# MA-Power.net
KiCad netlist of a schematic drawn in Altium Designer
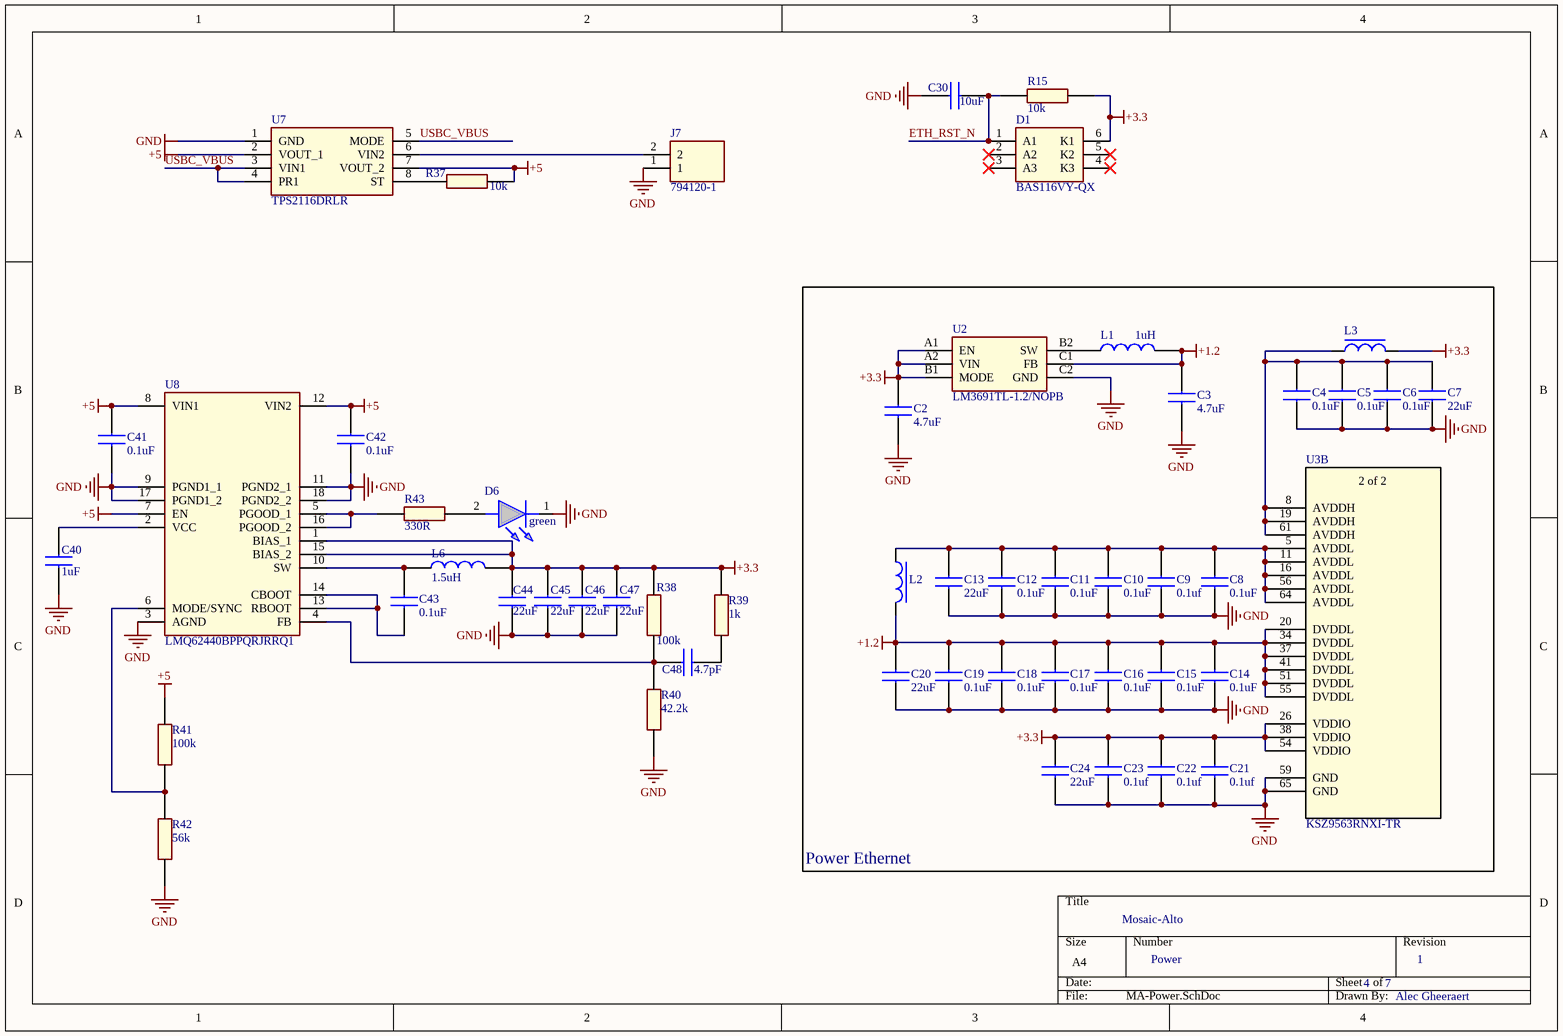
[diagram p0: MA-Power.SchDoc]

(export (version "E")
  (design (tool "Eeschema 10.0.6"))
  (components
    (comp (ref "C2")
      (value "4.7uF")
      (footprint "CAPC1608X100N")
      (description "0603 4.7µF")
      (fields (field (name "MANUFACTURER") "Walsin") (field (name "TOLERANCE") "20%"))
      (libsource (lib "Ghrt") (part "0603X475M6R3CT"))
    )
    (comp (ref "C3")
      (value "4.7uF")
      (footprint "CAPC1608X100N")
      (description "0603 4.7µF")
      (fields (field (name "MANUFACTURER") "Walsin") (field (name "TOLERANCE") "20%"))
      (libsource (lib "Ghrt") (part "0603X475M6R3CT"))
    )
    (comp (ref "C4")
      (value "0.1uF")
      (footprint "CAPC1005X55N")
      (description "0402I 0.1µF")
      (fields (field (name "MANUFACTURER") "Walsin") (field (name "TOLERANCE") "10%"))
      (libsource (lib "Ghrt") (part "MG15B104K100CT"))
    )
    (comp (ref "C5")
      (value "0.1uF")
      (footprint "CAPC1005X55N")
      (description "0402I 0.1µF")
      (fields (field (name "MANUFACTURER") "Walsin") (field (name "TOLERANCE") "10%"))
      (libsource (lib "Ghrt") (part "MG15B104K100CT"))
    )
    (comp (ref "C6")
      (value "0.1uF")
      (footprint "CAPC1005X55N")
      (description "0402I 0.1µF")
      (fields (field (name "MANUFACTURER") "Walsin") (field (name "TOLERANCE") "10%"))
      (libsource (lib "Ghrt") (part "MG15B104K100CT"))
    )
    (comp (ref "C7")
      (value "22uF")
      (footprint "CAPC2012X145N")
      (description "0805 22µF")
      (fields (field (name "MANUFACTURER") "Walsin") (field (name "TOLERANCE") "10%"))
      (libsource (lib "Ghrt") (part "0805X226K6R3CT"))
    )
    (comp (ref "C8")
      (value "0.1uF")
      (footprint "CAPC1005X55N")
      (description "0402I 0.1µF")
      (fields (field (name "MANUFACTURER") "Walsin") (field (name "TOLERANCE") "10%"))
      (libsource (lib "Ghrt") (part "MG15B104K100CT"))
    )
    (comp (ref "C9")
      (value "0.1uf")
      (footprint "CAPC1005X55N")
      (description "0402I 0.1µF")
      (fields (field (name "MANUFACTURER") "Walsin") (field (name "TOLERANCE") "10%"))
      (libsource (lib "Ghrt") (part "MG15B104K100CT"))
    )
    (comp (ref "C10")
      (value "0.1uF")
      (footprint "CAPC1005X55N")
      (description "0402I 0.1µF")
      (fields (field (name "MANUFACTURER") "Walsin") (field (name "TOLERANCE") "10%"))
      (libsource (lib "Ghrt") (part "MG15B104K100CT"))
    )
    (comp (ref "C11")
      (value "0.1uF")
      (footprint "CAPC1005X55N")
      (description "0402I 0.1µF")
      (fields (field (name "MANUFACTURER") "Walsin") (field (name "TOLERANCE") "10%"))
      (libsource (lib "Ghrt") (part "MG15B104K100CT"))
    )
    (comp (ref "C12")
      (value "0.1uF")
      (footprint "CAPC1005X55N")
      (description "0402I 0.1µF")
      (fields (field (name "MANUFACTURER") "Walsin") (field (name "TOLERANCE") "10%"))
      (libsource (lib "Ghrt") (part "MG15B104K100CT"))
    )
    (comp (ref "C13")
      (value "22uF")
      (footprint "CAPC2012X145N")
      (description "0805 22µF")
      (fields (field (name "MANUFACTURER") "Walsin") (field (name "TOLERANCE") "10%"))
      (libsource (lib "Ghrt") (part "0805X226K6R3CT"))
    )
    (comp (ref "C14")
      (value "0.1uF")
      (footprint "CAPC1005X55N")
      (description "0402I 0.1µF")
      (fields (field (name "MANUFACTURER") "Walsin") (field (name "TOLERANCE") "10%"))
      (libsource (lib "Ghrt") (part "MG15B104K100CT"))
    )
    (comp (ref "C15")
      (value "0.1uF")
      (footprint "CAPC1005X55N")
      (description "0402I 0.1µF")
      (fields (field (name "MANUFACTURER") "Walsin") (field (name "TOLERANCE") "10%"))
      (libsource (lib "Ghrt") (part "MG15B104K100CT"))
    )
    (comp (ref "C16")
      (value "0.1uF")
      (footprint "CAPC1005X55N")
      (description "0402I 0.1µF")
      (fields (field (name "MANUFACTURER") "Walsin") (field (name "TOLERANCE") "10%"))
      (libsource (lib "Ghrt") (part "MG15B104K100CT"))
    )
    (comp (ref "C17")
      (value "0.1uF")
      (footprint "CAPC1005X55N")
      (description "0402I 0.1µF")
      (fields (field (name "MANUFACTURER") "Walsin") (field (name "TOLERANCE") "10%"))
      (libsource (lib "Ghrt") (part "MG15B104K100CT"))
    )
    (comp (ref "C18")
      (value "0.1uF")
      (footprint "CAPC1005X55N")
      (description "0402I 0.1µF")
      (fields (field (name "MANUFACTURER") "Walsin") (field (name "TOLERANCE") "10%"))
      (libsource (lib "Ghrt") (part "MG15B104K100CT"))
    )
    (comp (ref "C19")
      (value "0.1uF")
      (footprint "CAPC1005X55N")
      (description "0402I 0.1µF")
      (fields (field (name "MANUFACTURER") "Walsin") (field (name "TOLERANCE") "10%"))
      (libsource (lib "Ghrt") (part "MG15B104K100CT"))
    )
    (comp (ref "C20")
      (value "22uF")
      (footprint "CAPC2012X145N")
      (description "0805 22µF")
      (fields (field (name "MANUFACTURER") "Walsin") (field (name "TOLERANCE") "10%"))
      (libsource (lib "Ghrt") (part "0805X226K6R3CT"))
    )
    (comp (ref "C21")
      (value "0.1uf")
      (footprint "CAPC1005X55N")
      (description "0402I 0.1µF")
      (fields (field (name "MANUFACTURER") "Walsin") (field (name "TOLERANCE") "10%"))
      (libsource (lib "Ghrt") (part "MG15B104K100CT"))
    )
    (comp (ref "C22")
      (value "0.1uf")
      (footprint "CAPC1005X55N")
      (description "0402I 0.1µF")
      (fields (field (name "MANUFACTURER") "Walsin") (field (name "TOLERANCE") "10%"))
      (libsource (lib "Ghrt") (part "MG15B104K100CT"))
    )
    (comp (ref "C23")
      (value "0.1uf")
      (footprint "CAPC1005X55N")
      (description "0402I 0.1µF")
      (fields (field (name "MANUFACTURER") "Walsin") (field (name "TOLERANCE") "10%"))
      (libsource (lib "Ghrt") (part "MG15B104K100CT"))
    )
    (comp (ref "C24")
      (value "22uF")
      (footprint "CAPC2012X145N")
      (description "0805 22µF")
      (fields (field (name "MANUFACTURER") "Walsin") (field (name "TOLERANCE") "10%"))
      (libsource (lib "Ghrt") (part "0805X226K6R3CT"))
    )
    (comp (ref "C30")
      (value "10uF")
      (footprint "CAPC1608X100N")
      (description "0603 10µF")
      (fields (field (name "MANUFACTURER") "Walsin") (field (name "TOLERANCE") "10%"))
      (libsource (lib "Ghrt") (part "0603X106K6R3CT"))
    )
    (comp (ref "C40")
      (value "1uF")
      (footprint "CAPC1608X100N")
      (description "0603 1µF")
      (fields (field (name "MANUFACTURER") "Walsin") (field (name "TOLERANCE") "10%"))
      (libsource (lib "Ghrt") (part "0603X105K6R3CT"))
    )
    (comp (ref "C41")
      (value "0.1uF")
      (footprint "CAPC2012X145N")
      (description "0805I 0.1µF")
      (fields (field (name "MANUFACTURER") "Walsin") (field (name "TOLERANCE") "10%"))
      (libsource (lib "Ghrt") (part "MG21B104K101CT"))
    )
    (comp (ref "C42")
      (value "0.1uF")
      (footprint "CAPC2012X145N")
      (description "0805I 0.1µF")
      (fields (field (name "MANUFACTURER") "Walsin") (field (name "TOLERANCE") "10%"))
      (libsource (lib "Ghrt") (part "MG21B104K101CT"))
    )
    (comp (ref "C43")
      (value "0.1uF")
      (footprint "CAPC1005X55N")
      (description "0402I 0.1µF")
      (fields (field (name "MANUFACTURER") "Walsin") (field (name "TOLERANCE") "10%"))
      (libsource (lib "Ghrt") (part "MG15B104K100CT"))
    )
    (comp (ref "C44")
      (value "22uF")
      (footprint "CAPC2012X145N")
      (description "0805 22µF")
      (fields (field (name "MANUFACTURER") "Walsin") (field (name "TOLERANCE") "10%"))
      (libsource (lib "Ghrt") (part "0805X226K6R3CT"))
    )
    (comp (ref "C45")
      (value "22uF")
      (footprint "CAPC2012X145N")
      (description "0805 22µF")
      (fields (field (name "MANUFACTURER") "Walsin") (field (name "TOLERANCE") "10%"))
      (libsource (lib "Ghrt") (part "0805X226K6R3CT"))
    )
    (comp (ref "C46")
      (value "22uF")
      (footprint "CAPC2012X145N")
      (description "0805 22µF")
      (fields (field (name "MANUFACTURER") "Walsin") (field (name "TOLERANCE") "10%"))
      (libsource (lib "Ghrt") (part "0805X226K6R3CT"))
    )
    (comp (ref "C47")
      (value "22uF")
      (footprint "CAPC2012X145N")
      (description "0805 22µF")
      (fields (field (name "MANUFACTURER") "Walsin") (field (name "TOLERANCE") "10%"))
      (libsource (lib "Ghrt") (part "0805X226K6R3CT"))
    )
    (comp (ref "C48")
      (value "4.7pF")
      (footprint "CAPC1608X87N")
      (description "0603 4.7pF")
      (fields (field (name "TOLERANCE") "5%") (field (name "MANUFACTURER") "Walsin"))
      (libsource (lib "Ghrt") (part "0603N4R7B500CT"))
    )
    (comp (ref "D1")
      (value "BAS116VY-QX")
      (footprint "BAS116VYQX")
      (description "Triple Diode Array")
      (fields (field (name "MANUFACTURER") "Nexperia"))
      (libsource (lib "Ghrt") (part "BAS116VY-QX"))
    )
    (comp (ref "D6")
      (value "green")
      (footprint "APT1608ZGCAMT")
      (description "0603 Green LED")
      (libsource (lib "Ghrt") (part "APT1608ZGC-AMT"))
    )
    (comp (ref "J7")
      (value "794120-1")
      (footprint "7941201")
      (description "Right Angle PCB Header")
      (libsource (lib "Ghrt") (part "794120-1"))
    )
    (comp (ref "L1")
      (value "1uH")
      (footprint "INDC2016X100N")
      (description "1µH Inductor")
      (fields (field (name "TOLERANCE") "20%") (field (name "MANUFACTURER") "TDK"))
      (libsource (lib "Ghrt") (part "MLP2016H1R0MT0S1"))
    )
    (comp (ref "L2")
      (value "MPZ1608S121ATDH5")
      (footprint "BEADC1608X75N")
      (description "0603I 120ohms Ferrite Bead")
      (fields (field (name "TOLERANCE") "25%") (field (name "MANUFACTURER") "TDK"))
      (libsource (lib "Ghrt") (part "MPZ1608S121ATDH5"))
    )
    (comp (ref "L3")
      (value "MPZ1608S121ATDH5")
      (footprint "BEADC1608X75N")
      (description "0603I 120ohms Ferrite Bead")
      (fields (field (name "TOLERANCE") "25%") (field (name "MANUFACTURER") "TDK"))
      (libsource (lib "Ghrt") (part "MPZ1608S121ATDH5"))
    )
    (comp (ref "L6")
      (value "1.5uH")
      (footprint "INDC1005X55N")
      (description "1.5uH Inductor")
      (libsource (lib "Ghrt") (part "MLF1005G1R5JTD25"))
    )
    (comp (ref "R15")
      (value "10k")
      (footprint "RESC1005X40N")
      (description "0402I 10k")
      (fields (field (name "MANUFACTURER") "Walsin") (field (name "TOLERANCE") "1%"))
      (libsource (lib "") (part "WR04X1002FTL_1"))
    )
    (comp (ref "R37")
      (value "10k")
      (footprint "RESC1005X40N")
      (description "0402I 10k")
      (fields (field (name "MANUFACTURER") "Walsin") (field (name "TOLERANCE") "1%"))
      (libsource (lib "Ghrt") (part "WR04X1002FTL"))
    )
    (comp (ref "R38")
      (value "100k")
      (footprint "RESC1005X40N")
      (description "0402I 100k")
      (fields (field (name "MANUFACTURER") "Walsin") (field (name "TOLERANCE") "1%"))
      (libsource (lib "") (part "WR04X1003FTL_1"))
    )
    (comp (ref "R39")
      (value "1k")
      (footprint "RESC1005X40N")
      (description "0402I 1k")
      (fields (field (name "MANUFACTURER") "Walsin") (field (name "TOLERANCE") "1%"))
      (libsource (lib "Ghrt") (part "WR04X1001FTL"))
    )
    (comp (ref "R40")
      (value "42.2k")
      (footprint "RESC1005X40N")
      (description "0402I 42.2k")
      (fields (field (name "TOLERANCE") "1%") (field (name "MANUFACTURER") "Walsin"))
      (libsource (lib "Ghrt") (part "WR04X4222FTL"))
    )
    (comp (ref "R41")
      (value "100k")
      (footprint "RESC1005X40N")
      (description "0402I 100k")
      (fields (field (name "MANUFACTURER") "Walsin") (field (name "TOLERANCE") "1%"))
      (libsource (lib "Ghrt") (part "WR04X1003FTL"))
    )
    (comp (ref "R42")
      (value "56k")
      (footprint "RESC1005X40N")
      (description "0402I 56k")
      (fields (field (name "TOLERANCE") "1%") (field (name "MANUFACTURER") "Walsin"))
      (libsource (lib "Ghrt") (part "WR04X5602FTL"))
    )
    (comp (ref "R43")
      (value "330R")
      (footprint "RESC1005X40N")
      (description "0402I 330")
      (fields (field (name "TOLERANCE") "1%") (field (name "MANUFACTURER") "Walsin"))
      (libsource (lib "Ghrt") (part "WR04X3300FTL"))
    )
    (comp (ref "U2")
      (value "LM3691TL-1.2/NOPB")
      (footprint "BGA6C50P2X3_126X156X68")
      (description "1.2V 1A Buck Converter")
      (fields (field (name "MANUFACTURER") "Texas Instruments"))
      (libsource (lib "Ghrt") (part "LM3691TL-1.2_NOPB"))
    )
    (comp (ref "U3")
      (value "KSZ9563RNXI-TR")
      (footprint "VQFN64_NX_MCH")
      (description "3-Port Gigabit Ethernet Switch")
      (fields (field (name "MANUFACTURER") "Texas Instruments"))
      (libsource (lib "Ghrt") (part "KSZ9563RNXI-TR"))
    )
    (comp (ref "U7")
      (value "TPS2116DRLR")
      (footprint "SOTFL50P160X60-8N")
      (description "2.5A Power Multiplexer")
      (fields (field (name "MANUFACTURER") "Texas Instruments"))
      (libsource (lib "Ghrt") (part "TPS2116DRLR"))
    )
    (comp (ref "U8")
      (value "LMQ62440BPPQRJRRQ1")
      (footprint "LMQ62440BPPQRJRRQ1")
      (description "3.3V 4A Switching Voltage Regulator")
      (fields (field (name "MANUFACTURER") "Texas Instruments"))
      (libsource (lib "Ghrt") (part "LMQ62440BPPQRJRRQ1"))
    )
  )
  (nets
    (net (code "1") (name "+1.2") (class "Default")
      (node (ref "C14") (pin "1") (pinfunction "1_1") (pintype "passive"))
      (node (ref "C15") (pin "1") (pinfunction "1_1") (pintype "passive"))
      (node (ref "C16") (pin "1") (pinfunction "1_1") (pintype "passive"))
      (node (ref "C17") (pin "1") (pinfunction "1_1") (pintype "passive"))
      (node (ref "C18") (pin "1") (pinfunction "1_1") (pintype "passive"))
      (node (ref "C19") (pin "1") (pinfunction "1_1") (pintype "passive"))
      (node (ref "C20") (pin "1") (pinfunction "1_1") (pintype "passive"))
      (node (ref "C3") (pin "1") (pinfunction "1_1") (pintype "passive"))
      (node (ref "L1") (pin "2") (pinfunction "2_2") (pintype "passive"))
      (node (ref "L2") (pin "2") (pinfunction "2_2") (pintype "passive"))
      (node (ref "U2") (pin "C1") (pinfunction "FB_C1") (pintype "passive"))
      (node (ref "U3") (pin "20") (pinfunction "DVDDL_20") (pintype "power_in"))
      (node (ref "U3") (pin "34") (pinfunction "DVDDL_34") (pintype "power_in"))
      (node (ref "U3") (pin "37") (pinfunction "DVDDL_37") (pintype "power_in"))
      (node (ref "U3") (pin "41") (pinfunction "DVDDL_41") (pintype "power_in"))
      (node (ref "U3") (pin "51") (pinfunction "DVDDL_51") (pintype "power_in"))
      (node (ref "U3") (pin "55") (pinfunction "DVDDL_55") (pintype "power_in"))
    )
    (net (code "2") (name "+3.3") (class "Default")
      (node (ref "C2") (pin "1") (pinfunction "1_1") (pintype "passive"))
      (node (ref "C21") (pin "1") (pinfunction "1_1") (pintype "passive"))
      (node (ref "C22") (pin "1") (pinfunction "1_1") (pintype "passive"))
      (node (ref "C23") (pin "1") (pinfunction "1_1") (pintype "passive"))
      (node (ref "C24") (pin "1") (pinfunction "1_1") (pintype "passive"))
      (node (ref "C44") (pin "1") (pinfunction "1_1") (pintype "passive"))
      (node (ref "C45") (pin "1") (pinfunction "1_1") (pintype "passive"))
      (node (ref "C46") (pin "1") (pinfunction "1_1") (pintype "passive"))
      (node (ref "C47") (pin "1") (pinfunction "1_1") (pintype "passive"))
      (node (ref "D1") (pin "6") (pinfunction "K1_6") (pintype "passive"))
      (node (ref "L3") (pin "2") (pinfunction "2_2") (pintype "passive"))
      (node (ref "L6") (pin "2") (pinfunction "2_2") (pintype "passive"))
      (node (ref "R15") (pin "1") (pinfunction "1_1") (pintype "passive"))
      (node (ref "R38") (pin "1") (pinfunction "1_1") (pintype "passive"))
      (node (ref "R39") (pin "2") (pinfunction "2_2") (pintype "passive"))
      (node (ref "U2") (pin "A1") (pinfunction "EN_A1") (pintype "passive"))
      (node (ref "U2") (pin "A2") (pinfunction "VIN_A2") (pintype "passive"))
      (node (ref "U2") (pin "B1") (pinfunction "MODE_B1") (pintype "passive"))
      (node (ref "U3") (pin "26") (pinfunction "VDDIO_26") (pintype "power_in"))
      (node (ref "U3") (pin "38") (pinfunction "VDDIO_38") (pintype "power_in"))
      (node (ref "U3") (pin "54") (pinfunction "VDDIO_54") (pintype "power_in"))
      (node (ref "U8") (pin "1") (pinfunction "BIAS_1_1") (pintype "passive"))
      (node (ref "U8") (pin "15") (pinfunction "BIAS_2_15") (pintype "passive"))
    )
    (net (code "3") (name "+5") (class "Default")
      (node (ref "C41") (pin "1") (pinfunction "1_1") (pintype "passive"))
      (node (ref "C42") (pin "1") (pinfunction "1_1") (pintype "passive"))
      (node (ref "R37") (pin "2") (pinfunction "2_2") (pintype "passive"))
      (node (ref "R41") (pin "2") (pinfunction "2_2") (pintype "passive"))
      (node (ref "U7") (pin "2") (pinfunction "VOUT_1_2") (pintype "passive"))
      (node (ref "U7") (pin "7") (pinfunction "VOUT_2_7") (pintype "passive"))
      (node (ref "U8") (pin "12") (pinfunction "VIN2_12") (pintype "passive"))
      (node (ref "U8") (pin "7") (pinfunction "EN_7") (pintype "passive"))
      (node (ref "U8") (pin "8") (pinfunction "VIN1_8") (pintype "passive"))
    )
    (net (code "4") (name "/ETH_RST_N") (class "Default")
      (node (ref "C30") (pin "1") (pinfunction "1_1") (pintype "passive"))
      (node (ref "D1") (pin "1") (pinfunction "A1_1") (pintype "passive"))
      (node (ref "R15") (pin "2") (pinfunction "2_2") (pintype "passive"))
    )
    (net (code "5") (name "/USBC_VBUS") (class "Default")
      (node (ref "U7") (pin "3") (pinfunction "VIN1_3") (pintype "passive"))
      (node (ref "U7") (pin "4") (pinfunction "PR1_4") (pintype "passive"))
      (node (ref "U7") (pin "5") (pinfunction "MODE_5") (pintype "passive"))
    )
    (net (code "6") (name "GND") (class "Default")
      (node (ref "C10") (pin "2") (pinfunction "2_2") (pintype "passive"))
      (node (ref "C11") (pin "2") (pinfunction "2_2") (pintype "passive"))
      (node (ref "C12") (pin "2") (pinfunction "2_2") (pintype "passive"))
      (node (ref "C13") (pin "2") (pinfunction "2_2") (pintype "passive"))
      (node (ref "C14") (pin "2") (pinfunction "2_2") (pintype "passive"))
      (node (ref "C15") (pin "2") (pinfunction "2_2") (pintype "passive"))
      (node (ref "C16") (pin "2") (pinfunction "2_2") (pintype "passive"))
      (node (ref "C17") (pin "2") (pinfunction "2_2") (pintype "passive"))
      (node (ref "C18") (pin "2") (pinfunction "2_2") (pintype "passive"))
      (node (ref "C19") (pin "2") (pinfunction "2_2") (pintype "passive"))
      (node (ref "C2") (pin "2") (pinfunction "2_2") (pintype "passive"))
      (node (ref "C20") (pin "2") (pinfunction "2_2") (pintype "passive"))
      (node (ref "C21") (pin "2") (pinfunction "2_2") (pintype "passive"))
      (node (ref "C22") (pin "2") (pinfunction "2_2") (pintype "passive"))
      (node (ref "C23") (pin "2") (pinfunction "2_2") (pintype "passive"))
      (node (ref "C24") (pin "2") (pinfunction "2_2") (pintype "passive"))
      (node (ref "C3") (pin "2") (pinfunction "2_2") (pintype "passive"))
      (node (ref "C30") (pin "2") (pinfunction "2_2") (pintype "passive"))
      (node (ref "C4") (pin "2") (pinfunction "2_2") (pintype "passive"))
      (node (ref "C40") (pin "2") (pinfunction "2_2") (pintype "passive"))
      (node (ref "C41") (pin "2") (pinfunction "2_2") (pintype "passive"))
      (node (ref "C42") (pin "2") (pinfunction "2_2") (pintype "passive"))
      (node (ref "C44") (pin "2") (pinfunction "2_2") (pintype "passive"))
      (node (ref "C45") (pin "2") (pinfunction "2_2") (pintype "passive"))
      (node (ref "C46") (pin "2") (pinfunction "2_2") (pintype "passive"))
      (node (ref "C47") (pin "2") (pinfunction "2_2") (pintype "passive"))
      (node (ref "C5") (pin "2") (pinfunction "2_2") (pintype "passive"))
      (node (ref "C6") (pin "2") (pinfunction "2_2") (pintype "passive"))
      (node (ref "C7") (pin "2") (pinfunction "2_2") (pintype "passive"))
      (node (ref "C8") (pin "2") (pinfunction "2_2") (pintype "passive"))
      (node (ref "C9") (pin "2") (pinfunction "2_2") (pintype "passive"))
      (node (ref "D6") (pin "1") (pinfunction "K_1") (pintype "passive"))
      (node (ref "J7") (pin "1") (pinfunction "1_1") (pintype "passive"))
      (node (ref "R40") (pin "2") (pinfunction "2_2") (pintype "passive"))
      (node (ref "R42") (pin "2") (pinfunction "2_2") (pintype "passive"))
      (node (ref "U2") (pin "C2") (pinfunction "GND_C2") (pintype "passive"))
      (node (ref "U3") (pin "59") (pinfunction "GND_59") (pintype "power_in"))
      (node (ref "U3") (pin "65") (pinfunction "GND_65") (pintype "power_in"))
      (node (ref "U7") (pin "1") (pinfunction "GND_1") (pintype "passive"))
      (node (ref "U8") (pin "11") (pinfunction "PGND2_1_11") (pintype "passive"))
      (node (ref "U8") (pin "17") (pinfunction "PGND1_2_17") (pintype "passive"))
      (node (ref "U8") (pin "18") (pinfunction "PGND2_2_18") (pintype "passive"))
      (node (ref "U8") (pin "3") (pinfunction "AGND_3") (pintype "passive"))
      (node (ref "U8") (pin "9") (pinfunction "PGND1_1_9") (pintype "passive"))
    )
    (net (code "7") (name "Net-(C4-Pad1)") (class "Default")
      (node (ref "C4") (pin "1") (pinfunction "1_1") (pintype "passive"))
      (node (ref "C5") (pin "1") (pinfunction "1_1") (pintype "passive"))
      (node (ref "C6") (pin "1") (pinfunction "1_1") (pintype "passive"))
      (node (ref "C7") (pin "1") (pinfunction "1_1") (pintype "passive"))
      (node (ref "L3") (pin "1") (pinfunction "1_1") (pintype "passive"))
      (node (ref "U3") (pin "19") (pinfunction "AVDDH_19") (pintype "power_in"))
      (node (ref "U3") (pin "61") (pinfunction "AVDDH_61") (pintype "power_in"))
      (node (ref "U3") (pin "8") (pinfunction "AVDDH_8") (pintype "power_in"))
    )
    (net (code "8") (name "Net-(C10-Pad1)") (class "Default")
      (node (ref "C10") (pin "1") (pinfunction "1_1") (pintype "passive"))
      (node (ref "C11") (pin "1") (pinfunction "1_1") (pintype "passive"))
      (node (ref "C12") (pin "1") (pinfunction "1_1") (pintype "passive"))
      (node (ref "C13") (pin "1") (pinfunction "1_1") (pintype "passive"))
      (node (ref "C8") (pin "1") (pinfunction "1_1") (pintype "passive"))
      (node (ref "C9") (pin "1") (pinfunction "1_1") (pintype "passive"))
      (node (ref "L2") (pin "1") (pinfunction "1_1") (pintype "passive"))
      (node (ref "U3") (pin "11") (pinfunction "AVDDL_11") (pintype "power_in"))
      (node (ref "U3") (pin "16") (pinfunction "AVDDL_16") (pintype "power_in"))
      (node (ref "U3") (pin "5") (pinfunction "AVDDL_5") (pintype "power_in"))
      (node (ref "U3") (pin "56") (pinfunction "AVDDL_56") (pintype "power_in"))
      (node (ref "U3") (pin "64") (pinfunction "AVDDL_64") (pintype "power_in"))
    )
    (net (code "9") (name "Net-(C48-Pad2)") (class "Default")
      (node (ref "C48") (pin "2") (pinfunction "2_2") (pintype "passive"))
      (node (ref "R39") (pin "1") (pinfunction "1_1") (pintype "passive"))
    )
    (net (code "10") (name "Net-(D6-A)") (class "Default")
      (node (ref "D6") (pin "2") (pinfunction "A_2") (pintype "passive"))
      (node (ref "R43") (pin "2") (pinfunction "2_2") (pintype "passive"))
    )
    (net (code "11") (name "Net-(U2-SW)") (class "Default")
      (node (ref "L1") (pin "1") (pinfunction "1_1") (pintype "passive"))
      (node (ref "U2") (pin "B2") (pinfunction "SW_B2") (pintype "passive"))
    )
    (net (code "12") (name "Net-(U7-ST)") (class "Default")
      (node (ref "R37") (pin "1") (pinfunction "1_1") (pintype "passive"))
      (node (ref "U7") (pin "8") (pinfunction "ST_8") (pintype "passive"))
    )
    (net (code "13") (name "Net-(U7-VIN2)") (class "Default")
      (node (ref "J7") (pin "2") (pinfunction "2_2") (pintype "passive"))
      (node (ref "U7") (pin "6") (pinfunction "VIN2_6") (pintype "passive"))
    )
    (net (code "14") (name "Net-(U8-CBOOT)") (class "Default")
      (node (ref "C43") (pin "2") (pinfunction "2_2") (pintype "passive"))
      (node (ref "U8") (pin "13") (pinfunction "RBOOT_13") (pintype "passive"))
      (node (ref "U8") (pin "14") (pinfunction "CBOOT_14") (pintype "passive"))
    )
    (net (code "15") (name "Net-(U8-FB)") (class "Default")
      (node (ref "C48") (pin "1") (pinfunction "1_1") (pintype "passive"))
      (node (ref "R38") (pin "2") (pinfunction "2_2") (pintype "passive"))
      (node (ref "R40") (pin "1") (pinfunction "1_1") (pintype "passive"))
      (node (ref "U8") (pin "4") (pinfunction "FB_4") (pintype "passive"))
    )
    (net (code "16") (name "Net-(U8-MODE{slash}SYNC)") (class "Default")
      (node (ref "R41") (pin "1") (pinfunction "1_1") (pintype "passive"))
      (node (ref "R42") (pin "1") (pinfunction "1_1") (pintype "passive"))
      (node (ref "U8") (pin "6") (pinfunction "MODE/SYNC_6") (pintype "passive"))
    )
    (net (code "17") (name "Net-(U8-PGOOD_1)") (class "Default")
      (node (ref "R43") (pin "1") (pinfunction "1_1") (pintype "passive"))
      (node (ref "U8") (pin "16") (pinfunction "PGOOD_2_16") (pintype "passive"))
      (node (ref "U8") (pin "5") (pinfunction "PGOOD_1_5") (pintype "passive"))
    )
    (net (code "18") (name "Net-(U8-SW)") (class "Default")
      (node (ref "C43") (pin "1") (pinfunction "1_1") (pintype "passive"))
      (node (ref "L6") (pin "1") (pinfunction "1_1") (pintype "passive"))
      (node (ref "U8") (pin "10") (pinfunction "SW_10") (pintype "passive"))
    )
    (net (code "19") (name "Net-(U8-VCC)") (class "Default")
      (node (ref "C40") (pin "1") (pinfunction "1_1") (pintype "passive"))
      (node (ref "U8") (pin "2") (pinfunction "VCC_2") (pintype "passive"))
    )
    (net (code "20") (name "unconnected-(D1-A2-Pad2)") (class "Default")
      (node (ref "D1") (pin "2") (pinfunction "A2_2") (pintype "passive+no_connect"))
    )
    (net (code "21") (name "unconnected-(D1-A3-Pad3)") (class "Default")
      (node (ref "D1") (pin "3") (pinfunction "A3_3") (pintype "passive+no_connect"))
    )
    (net (code "22") (name "unconnected-(D1-K2-Pad5)") (class "Default")
      (node (ref "D1") (pin "5") (pinfunction "K2_5") (pintype "passive+no_connect"))
    )
    (net (code "23") (name "unconnected-(D1-K3-Pad4)") (class "Default")
      (node (ref "D1") (pin "4") (pinfunction "K3_4") (pintype "passive+no_connect"))
    )
  )
)
